# led-1.net
KiCad netlist of a schematic drawn in EAGLE
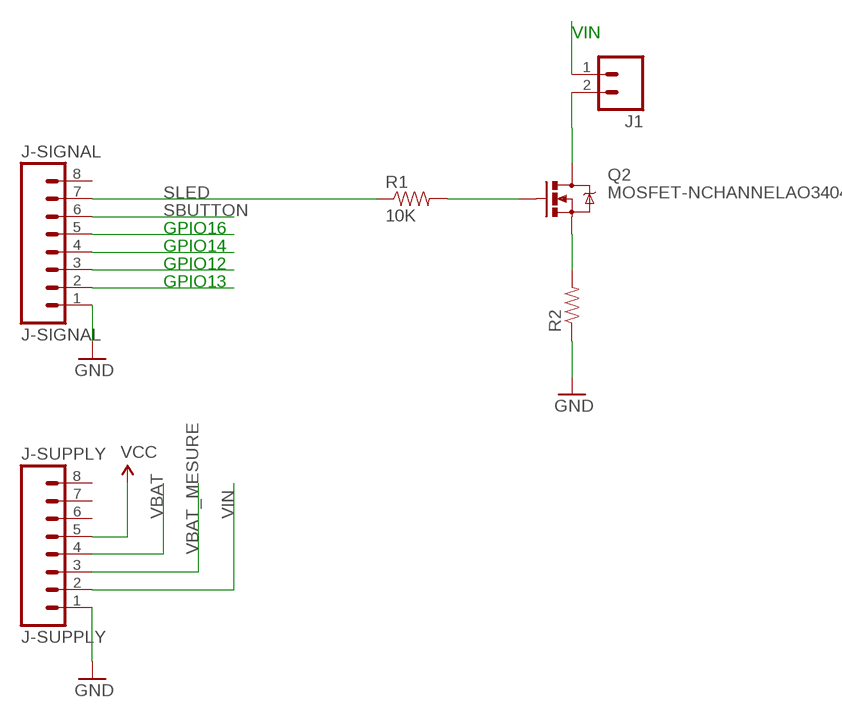
[diagram p0: schematic, sheet 1]

(export (version "E")
  (design (tool "Eeschema 10.0.6"))
  (components
    (comp (ref "J-SIGNAL")
      (value "J-SIGNAL")
      (footprint "eagle-import:1X08_ROUND")
      (libsource (lib "eagle-import") (part "M08"))
    )
    (comp (ref "J-SUPPLY")
      (value "J-SUPPLY")
      (footprint "eagle-import:1X08_ROUND")
      (libsource (lib "eagle-import") (part "M08"))
    )
    (comp (ref "J1")
      (value "M02JST-PTH-VERT")
      (footprint "eagle-import:JST-2-PTH-VERT")
      (libsource (lib "eagle-import") (part "M02JST-PTH-VERT"))
    )
    (comp (ref "Q2")
      (value "MOSFET-NCHANNELAO3404A")
      (footprint "eagle-import:SOT23-3")
      (libsource (lib "eagle-import") (part "MOSFET-NCHANNELAO3404A"))
    )
    (comp (ref "R1")
      (value "10K")
      (footprint "eagle-import:0805")
      (libsource (lib "eagle-import") (part "RESISTOR0805-RES"))
    )
    (comp (ref "R2")
      (value "RESISTORPTH-1/2W")
      (footprint "eagle-import:AXIAL-0.5")
      (libsource (lib "eagle-import") (part "RESISTORPTH-1/2W"))
    )
  )
  (nets
    (net (code "1") (name "/SBUTTON") (class "Default")
      (node (ref "J-SIGNAL") (pin "6") (pinfunction "6_6") (pintype "passive"))
    )
    (net (code "2") (name "/SLED") (class "Default")
      (node (ref "J-SIGNAL") (pin "7") (pinfunction "7_7") (pintype "passive"))
      (node (ref "R1") (pin "1") (pinfunction "1_1") (pintype "passive"))
    )
    (net (code "3") (name "/VBAT") (class "Default")
      (node (ref "J-SUPPLY") (pin "4") (pinfunction "4_4") (pintype "passive"))
    )
    (net (code "4") (name "/VBAT_MESURE") (class "Default")
      (node (ref "J-SUPPLY") (pin "3") (pinfunction "3_3") (pintype "passive"))
    )
    (net (code "5") (name "/VIN") (class "Default")
      (node (ref "J-SUPPLY") (pin "2") (pinfunction "2_2") (pintype "passive"))
      (node (ref "J1") (pin "1") (pinfunction "1_1") (pintype "passive"))
    )
    (net (code "6") (name "GND") (class "Default")
      (node (ref "J-SIGNAL") (pin "1") (pinfunction "1_1") (pintype "passive"))
      (node (ref "J-SUPPLY") (pin "1") (pinfunction "1_1") (pintype "passive"))
      (node (ref "R2") (pin "P$1") (pinfunction "1_P$1") (pintype "passive"))
    )
    (net (code "7") (name "Net-(Q2-D)") (class "Default")
      (node (ref "J1") (pin "2") (pinfunction "2_2") (pintype "passive"))
      (node (ref "Q2") (pin "3") (pinfunction "D_3") (pintype "passive"))
    )
    (net (code "8") (name "Net-(Q2-G)") (class "Default")
      (node (ref "Q2") (pin "1") (pinfunction "G_1") (pintype "passive"))
      (node (ref "R1") (pin "2") (pinfunction "2_2") (pintype "passive"))
    )
    (net (code "9") (name "Net-(Q2-S)") (class "Default")
      (node (ref "Q2") (pin "2") (pinfunction "S_2") (pintype "passive"))
      (node (ref "R2") (pin "P$2") (pinfunction "2_P$2") (pintype "passive"))
    )
    (net (code "10") (name "VCC") (class "Default")
      (node (ref "J-SUPPLY") (pin "5") (pinfunction "5_5") (pintype "passive"))
    )
    (net (code "11") (name "unconnected-(J-SIGNAL-Pad2)") (class "Default")
      (node (ref "J-SIGNAL") (pin "2") (pinfunction "2_2") (pintype "passive"))
    )
    (net (code "12") (name "unconnected-(J-SIGNAL-Pad3)") (class "Default")
      (node (ref "J-SIGNAL") (pin "3") (pinfunction "3_3") (pintype "passive"))
    )
    (net (code "13") (name "unconnected-(J-SIGNAL-Pad4)") (class "Default")
      (node (ref "J-SIGNAL") (pin "4") (pinfunction "4_4") (pintype "passive"))
    )
    (net (code "14") (name "unconnected-(J-SIGNAL-Pad5)") (class "Default")
      (node (ref "J-SIGNAL") (pin "5") (pinfunction "5_5") (pintype "passive"))
    )
    (net (code "15") (name "unconnected-(J-SIGNAL-Pad8)") (class "Default")
      (node (ref "J-SIGNAL") (pin "8") (pinfunction "8_8") (pintype "passive"))
    )
    (net (code "16") (name "unconnected-(J-SUPPLY-Pad6)") (class "Default")
      (node (ref "J-SUPPLY") (pin "6") (pinfunction "6_6") (pintype "passive"))
    )
    (net (code "17") (name "unconnected-(J-SUPPLY-Pad7)") (class "Default")
      (node (ref "J-SUPPLY") (pin "7") (pinfunction "7_7") (pintype "passive"))
    )
    (net (code "18") (name "unconnected-(J-SUPPLY-Pad8)") (class "Default")
      (node (ref "J-SUPPLY") (pin "8") (pinfunction "8_8") (pintype "passive"))
    )
  )
)
